# SN76477_Synth.net
KiCad netlist of a schematic drawn in EAGLE
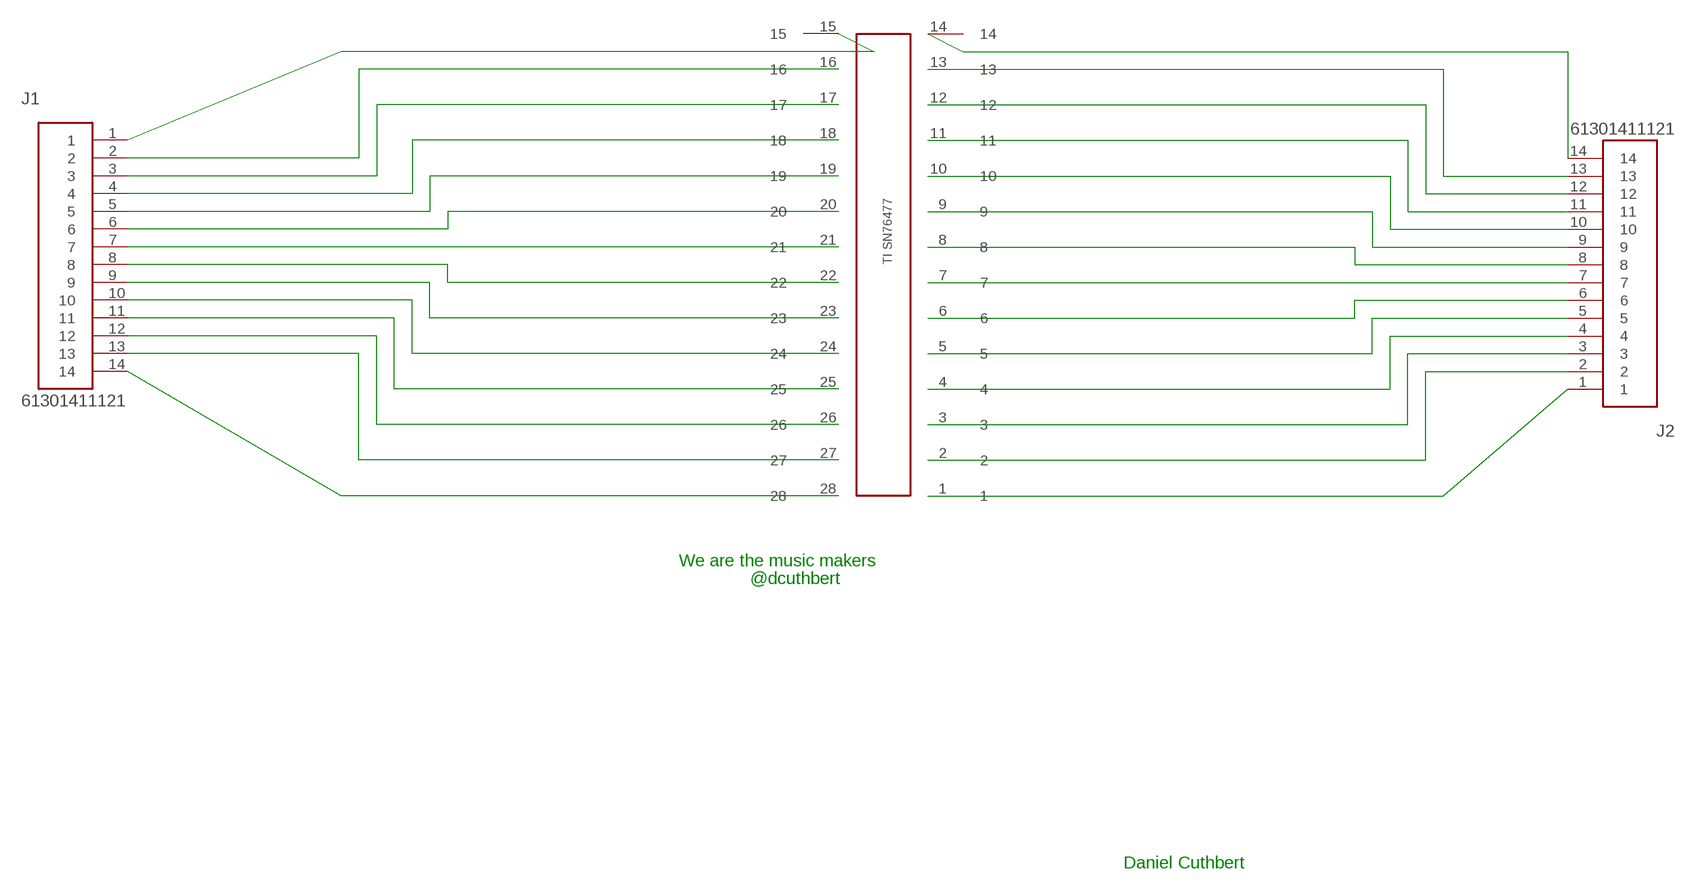
[diagram p0: schematic, sheet 1]

(export (version "E")
  (design (tool "Eeschema 10.0.6"))
  (components
    (comp (ref "J1")
      (value "61301411121")
      (footprint "eagle-import:61301411121")
      (fields
        (field (name "DIGIKEY_PART_NUMBER") "732-5325-ND")
        (field (name "MANUFACTURER") "Wurth Electronics Inc.")
        (field (name "CREATED_BY") "PCBLayout.com")
      )
      (libsource (lib "eagle-import") (part "61301411121"))
    )
    (comp (ref "J2")
      (value "61301411121")
      (footprint "eagle-import:61301411121")
      (fields
        (field (name "DIGIKEY_PART_NUMBER") "732-5325-ND")
        (field (name "MANUFACTURER") "Wurth Electronics Inc.")
        (field (name "CREATED_BY") "PCBLayout.com")
      )
      (libsource (lib "eagle-import") (part "61301411121"))
    )
    (comp (ref "U$1")
      (value "SN76477NOISEGENERATORSN76477")
      (footprint "eagle-import:SN76477NOISEGENERATOR")
      (libsource (lib "eagle-import") (part "SN76477NOISEGENERATORSN76477"))
    )
  )
  (nets
    (net (code "1") (name "Net-(J1-Pad1)") (class "Default")
      (node (ref "J1") (pin "1") (pinfunction "1_1") (pintype "passive"))
      (node (ref "U$1") (pin "15") (pinfunction "15_15") (pintype "bidirectional"))
    )
    (net (code "2") (name "Net-(J1-Pad2)") (class "Default")
      (node (ref "J1") (pin "2") (pinfunction "2_2") (pintype "passive"))
      (node (ref "U$1") (pin "16") (pinfunction "16_16") (pintype "bidirectional"))
    )
    (net (code "3") (name "Net-(J1-Pad3)") (class "Default")
      (node (ref "J1") (pin "3") (pinfunction "3_3") (pintype "passive"))
      (node (ref "U$1") (pin "17") (pinfunction "17_17") (pintype "bidirectional"))
    )
    (net (code "4") (name "Net-(J1-Pad4)") (class "Default")
      (node (ref "J1") (pin "4") (pinfunction "4_4") (pintype "passive"))
      (node (ref "U$1") (pin "18") (pinfunction "18_18") (pintype "bidirectional"))
    )
    (net (code "5") (name "Net-(J1-Pad5)") (class "Default")
      (node (ref "J1") (pin "5") (pinfunction "5_5") (pintype "passive"))
      (node (ref "U$1") (pin "19") (pinfunction "19_19") (pintype "bidirectional"))
    )
    (net (code "6") (name "Net-(J1-Pad6)") (class "Default")
      (node (ref "J1") (pin "6") (pinfunction "6_6") (pintype "passive"))
      (node (ref "U$1") (pin "20") (pinfunction "20_20") (pintype "bidirectional"))
    )
    (net (code "7") (name "Net-(J1-Pad7)") (class "Default")
      (node (ref "J1") (pin "7") (pinfunction "7_7") (pintype "passive"))
      (node (ref "U$1") (pin "21") (pinfunction "21_21") (pintype "bidirectional"))
    )
    (net (code "8") (name "Net-(J1-Pad8)") (class "Default")
      (node (ref "J1") (pin "8") (pinfunction "8_8") (pintype "passive"))
      (node (ref "U$1") (pin "22") (pinfunction "22_22") (pintype "bidirectional"))
    )
    (net (code "9") (name "Net-(J1-Pad9)") (class "Default")
      (node (ref "J1") (pin "9") (pinfunction "9_9") (pintype "passive"))
      (node (ref "U$1") (pin "23") (pinfunction "23_23") (pintype "bidirectional"))
    )
    (net (code "10") (name "Net-(J1-Pad10)") (class "Default")
      (node (ref "J1") (pin "10") (pinfunction "10_10") (pintype "passive"))
      (node (ref "U$1") (pin "24") (pinfunction "24_24") (pintype "bidirectional"))
    )
    (net (code "11") (name "Net-(J1-Pad11)") (class "Default")
      (node (ref "J1") (pin "11") (pinfunction "11_11") (pintype "passive"))
      (node (ref "U$1") (pin "25") (pinfunction "25_25") (pintype "bidirectional"))
    )
    (net (code "12") (name "Net-(J1-Pad12)") (class "Default")
      (node (ref "J1") (pin "12") (pinfunction "12_12") (pintype "passive"))
      (node (ref "U$1") (pin "26") (pinfunction "26_26") (pintype "bidirectional"))
    )
    (net (code "13") (name "Net-(J1-Pad13)") (class "Default")
      (node (ref "J1") (pin "13") (pinfunction "13_13") (pintype "passive"))
      (node (ref "U$1") (pin "27") (pinfunction "27_27") (pintype "bidirectional"))
    )
    (net (code "14") (name "Net-(J1-Pad14)") (class "Default")
      (node (ref "J1") (pin "14") (pinfunction "14_14") (pintype "passive"))
      (node (ref "U$1") (pin "28") (pinfunction "28_28") (pintype "bidirectional"))
    )
    (net (code "15") (name "Net-(J2-Pad1)") (class "Default")
      (node (ref "J2") (pin "1") (pinfunction "1_1") (pintype "passive"))
      (node (ref "U$1") (pin "1") (pinfunction "1_1") (pintype "bidirectional"))
    )
    (net (code "16") (name "Net-(J2-Pad2)") (class "Default")
      (node (ref "J2") (pin "2") (pinfunction "2_2") (pintype "passive"))
      (node (ref "U$1") (pin "2") (pinfunction "2_2") (pintype "bidirectional"))
    )
    (net (code "17") (name "Net-(J2-Pad3)") (class "Default")
      (node (ref "J2") (pin "3") (pinfunction "3_3") (pintype "passive"))
      (node (ref "U$1") (pin "3") (pinfunction "3_3") (pintype "bidirectional"))
    )
    (net (code "18") (name "Net-(J2-Pad4)") (class "Default")
      (node (ref "J2") (pin "4") (pinfunction "4_4") (pintype "passive"))
      (node (ref "U$1") (pin "4") (pinfunction "4_4") (pintype "bidirectional"))
    )
    (net (code "19") (name "Net-(J2-Pad5)") (class "Default")
      (node (ref "J2") (pin "5") (pinfunction "5_5") (pintype "passive"))
      (node (ref "U$1") (pin "5") (pinfunction "5_5") (pintype "bidirectional"))
    )
    (net (code "20") (name "Net-(J2-Pad6)") (class "Default")
      (node (ref "J2") (pin "6") (pinfunction "6_6") (pintype "passive"))
      (node (ref "U$1") (pin "6") (pinfunction "6_6") (pintype "bidirectional"))
    )
    (net (code "21") (name "Net-(J2-Pad7)") (class "Default")
      (node (ref "J2") (pin "7") (pinfunction "7_7") (pintype "passive"))
      (node (ref "U$1") (pin "7") (pinfunction "7_7") (pintype "bidirectional"))
    )
    (net (code "22") (name "Net-(J2-Pad8)") (class "Default")
      (node (ref "J2") (pin "8") (pinfunction "8_8") (pintype "passive"))
      (node (ref "U$1") (pin "8") (pinfunction "8_8") (pintype "bidirectional"))
    )
    (net (code "23") (name "Net-(J2-Pad9)") (class "Default")
      (node (ref "J2") (pin "9") (pinfunction "9_9") (pintype "passive"))
      (node (ref "U$1") (pin "9") (pinfunction "9_9") (pintype "bidirectional"))
    )
    (net (code "24") (name "Net-(J2-Pad10)") (class "Default")
      (node (ref "J2") (pin "10") (pinfunction "10_10") (pintype "passive"))
      (node (ref "U$1") (pin "10") (pinfunction "10_10") (pintype "bidirectional"))
    )
    (net (code "25") (name "Net-(J2-Pad11)") (class "Default")
      (node (ref "J2") (pin "11") (pinfunction "11_11") (pintype "passive"))
      (node (ref "U$1") (pin "11") (pinfunction "11_11") (pintype "bidirectional"))
    )
    (net (code "26") (name "Net-(J2-Pad12)") (class "Default")
      (node (ref "J2") (pin "12") (pinfunction "12_12") (pintype "passive"))
      (node (ref "U$1") (pin "12") (pinfunction "12_12") (pintype "bidirectional"))
    )
    (net (code "27") (name "Net-(J2-Pad13)") (class "Default")
      (node (ref "J2") (pin "13") (pinfunction "13_13") (pintype "passive"))
      (node (ref "U$1") (pin "13") (pinfunction "13_13") (pintype "bidirectional"))
    )
    (net (code "28") (name "Net-(J2-Pad14)") (class "Default")
      (node (ref "J2") (pin "14") (pinfunction "14_14") (pintype "passive"))
      (node (ref "U$1") (pin "14") (pinfunction "14_14") (pintype "bidirectional"))
    )
  )
)
